# LCD_side_Adalogger.net
KiCad netlist of a schematic drawn in EAGLE
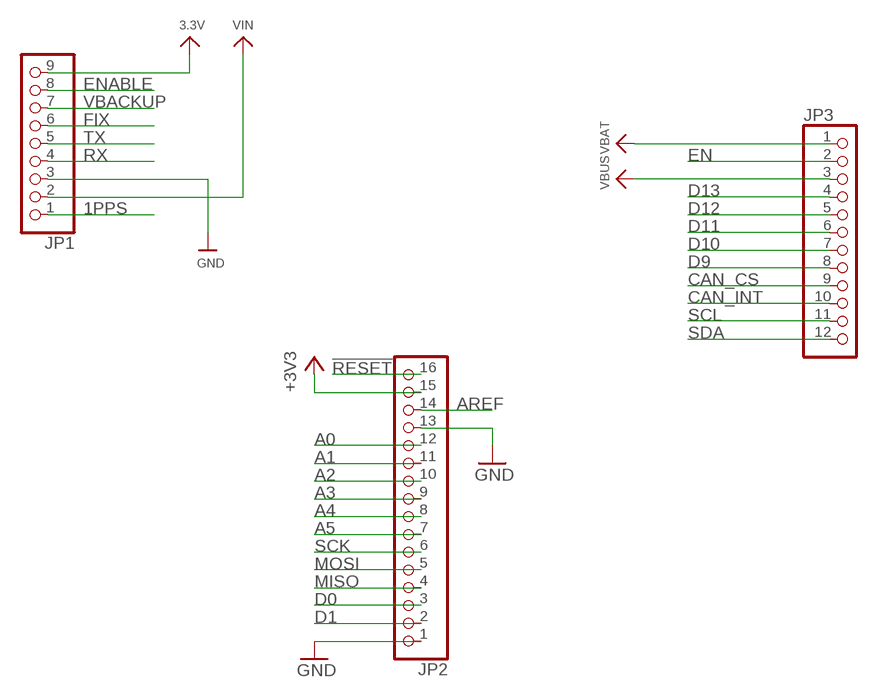
[diagram p0: schematic, sheet 1]

(export (version "E")
  (design (tool "Eeschema 10.0.6"))
  (components
    (comp (ref "JP1")
      (value "HEADER-1X970MIL")
      (footprint "eagle-import:1X09_ROUND_70")
      (libsource (lib "eagle-import") (part "HEADER-1X970MIL"))
    )
    (comp (ref "JP2")
      (value "HEADER-1X16ROUND")
      (footprint "eagle-import:1X16_ROUND")
      (libsource (lib "eagle-import") (part "HEADER-1X16ROUND"))
    )
    (comp (ref "JP3")
      (value "HEADER-1X12")
      (footprint "eagle-import:1X12_ROUND")
      (libsource (lib "eagle-import") (part "HEADER-1X12"))
    )
  )
  (nets
    (net (code "1") (name "+3V3") (class "Default")
      (node (ref "JP2") (pin "15") (pinfunction "15_15") (pintype "passive"))
    )
    (net (code "2") (name "/1PPS") (class "Default")
      (node (ref "JP1") (pin "1") (pinfunction "1_1") (pintype "passive"))
    )
    (net (code "3") (name "/A0") (class "Default")
      (node (ref "JP2") (pin "12") (pinfunction "12_12") (pintype "passive"))
    )
    (net (code "4") (name "/A1") (class "Default")
      (node (ref "JP2") (pin "11") (pinfunction "11_11") (pintype "passive"))
    )
    (net (code "5") (name "/A2") (class "Default")
      (node (ref "JP2") (pin "10") (pinfunction "10_10") (pintype "passive"))
    )
    (net (code "6") (name "/A3") (class "Default")
      (node (ref "JP2") (pin "9") (pinfunction "9_9") (pintype "passive"))
    )
    (net (code "7") (name "/A4") (class "Default")
      (node (ref "JP2") (pin "8") (pinfunction "8_8") (pintype "passive"))
    )
    (net (code "8") (name "/A5") (class "Default")
      (node (ref "JP2") (pin "7") (pinfunction "7_7") (pintype "passive"))
    )
    (net (code "9") (name "/AREF") (class "Default")
      (node (ref "JP2") (pin "14") (pinfunction "14_14") (pintype "passive"))
    )
    (net (code "10") (name "/CAN_CS") (class "Default")
      (node (ref "JP3") (pin "9") (pinfunction "9_9") (pintype "passive"))
    )
    (net (code "11") (name "/CAN_INT") (class "Default")
      (node (ref "JP3") (pin "10") (pinfunction "10_10") (pintype "passive"))
    )
    (net (code "12") (name "/D0") (class "Default")
      (node (ref "JP2") (pin "3") (pinfunction "3_3") (pintype "passive"))
    )
    (net (code "13") (name "/D1") (class "Default")
      (node (ref "JP2") (pin "2") (pinfunction "2_2") (pintype "passive"))
    )
    (net (code "14") (name "/D9") (class "Default")
      (node (ref "JP3") (pin "8") (pinfunction "8_8") (pintype "passive"))
    )
    (net (code "15") (name "/D10") (class "Default")
      (node (ref "JP3") (pin "7") (pinfunction "7_7") (pintype "passive"))
    )
    (net (code "16") (name "/D11") (class "Default")
      (node (ref "JP3") (pin "6") (pinfunction "6_6") (pintype "passive"))
    )
    (net (code "17") (name "/D12") (class "Default")
      (node (ref "JP3") (pin "5") (pinfunction "5_5") (pintype "passive"))
    )
    (net (code "18") (name "/D13") (class "Default")
      (node (ref "JP3") (pin "4") (pinfunction "4_4") (pintype "passive"))
    )
    (net (code "19") (name "/EN") (class "Default")
      (node (ref "JP3") (pin "2") (pinfunction "2_2") (pintype "passive"))
    )
    (net (code "20") (name "/ENABLE") (class "Default")
      (node (ref "JP1") (pin "8") (pinfunction "8_8") (pintype "passive"))
    )
    (net (code "21") (name "/FIX") (class "Default")
      (node (ref "JP1") (pin "6") (pinfunction "6_6") (pintype "passive"))
    )
    (net (code "22") (name "/MISO") (class "Default")
      (node (ref "JP2") (pin "4") (pinfunction "4_4") (pintype "passive"))
    )
    (net (code "23") (name "/MOSI") (class "Default")
      (node (ref "JP2") (pin "5") (pinfunction "5_5") (pintype "passive"))
    )
    (net (code "24") (name "/RX") (class "Default")
      (node (ref "JP1") (pin "4") (pinfunction "4_4") (pintype "passive"))
    )
    (net (code "25") (name "/SCK") (class "Default")
      (node (ref "JP2") (pin "6") (pinfunction "6_6") (pintype "passive"))
    )
    (net (code "26") (name "/SCL") (class "Default")
      (node (ref "JP3") (pin "11") (pinfunction "11_11") (pintype "passive"))
    )
    (net (code "27") (name "/SDA") (class "Default")
      (node (ref "JP3") (pin "12") (pinfunction "12_12") (pintype "passive"))
    )
    (net (code "28") (name "/TX") (class "Default")
      (node (ref "JP1") (pin "5") (pinfunction "5_5") (pintype "passive"))
    )
    (net (code "29") (name "/VBACKUP") (class "Default")
      (node (ref "JP1") (pin "7") (pinfunction "7_7") (pintype "passive"))
    )
    (net (code "30") (name "/~{RESET}") (class "Default")
      (node (ref "JP2") (pin "16") (pinfunction "16_16") (pintype "passive"))
    )
    (net (code "31") (name "3.3V") (class "Default")
      (node (ref "JP1") (pin "9") (pinfunction "9_9") (pintype "passive"))
    )
    (net (code "32") (name "GND") (class "Default")
      (node (ref "JP1") (pin "3") (pinfunction "3_3") (pintype "passive"))
      (node (ref "JP2") (pin "1") (pinfunction "1_1") (pintype "passive"))
      (node (ref "JP2") (pin "13") (pinfunction "13_13") (pintype "passive"))
    )
    (net (code "33") (name "VBAT") (class "Default")
      (node (ref "JP3") (pin "1") (pinfunction "1_1") (pintype "passive"))
    )
    (net (code "34") (name "VBUS") (class "Default")
      (node (ref "JP3") (pin "3") (pinfunction "3_3") (pintype "passive"))
    )
    (net (code "35") (name "VIN") (class "Default")
      (node (ref "JP1") (pin "2") (pinfunction "2_2") (pintype "passive"))
    )
  )
)
